# Offset.net
KiCad netlist of a schematic drawn in Altium Designer
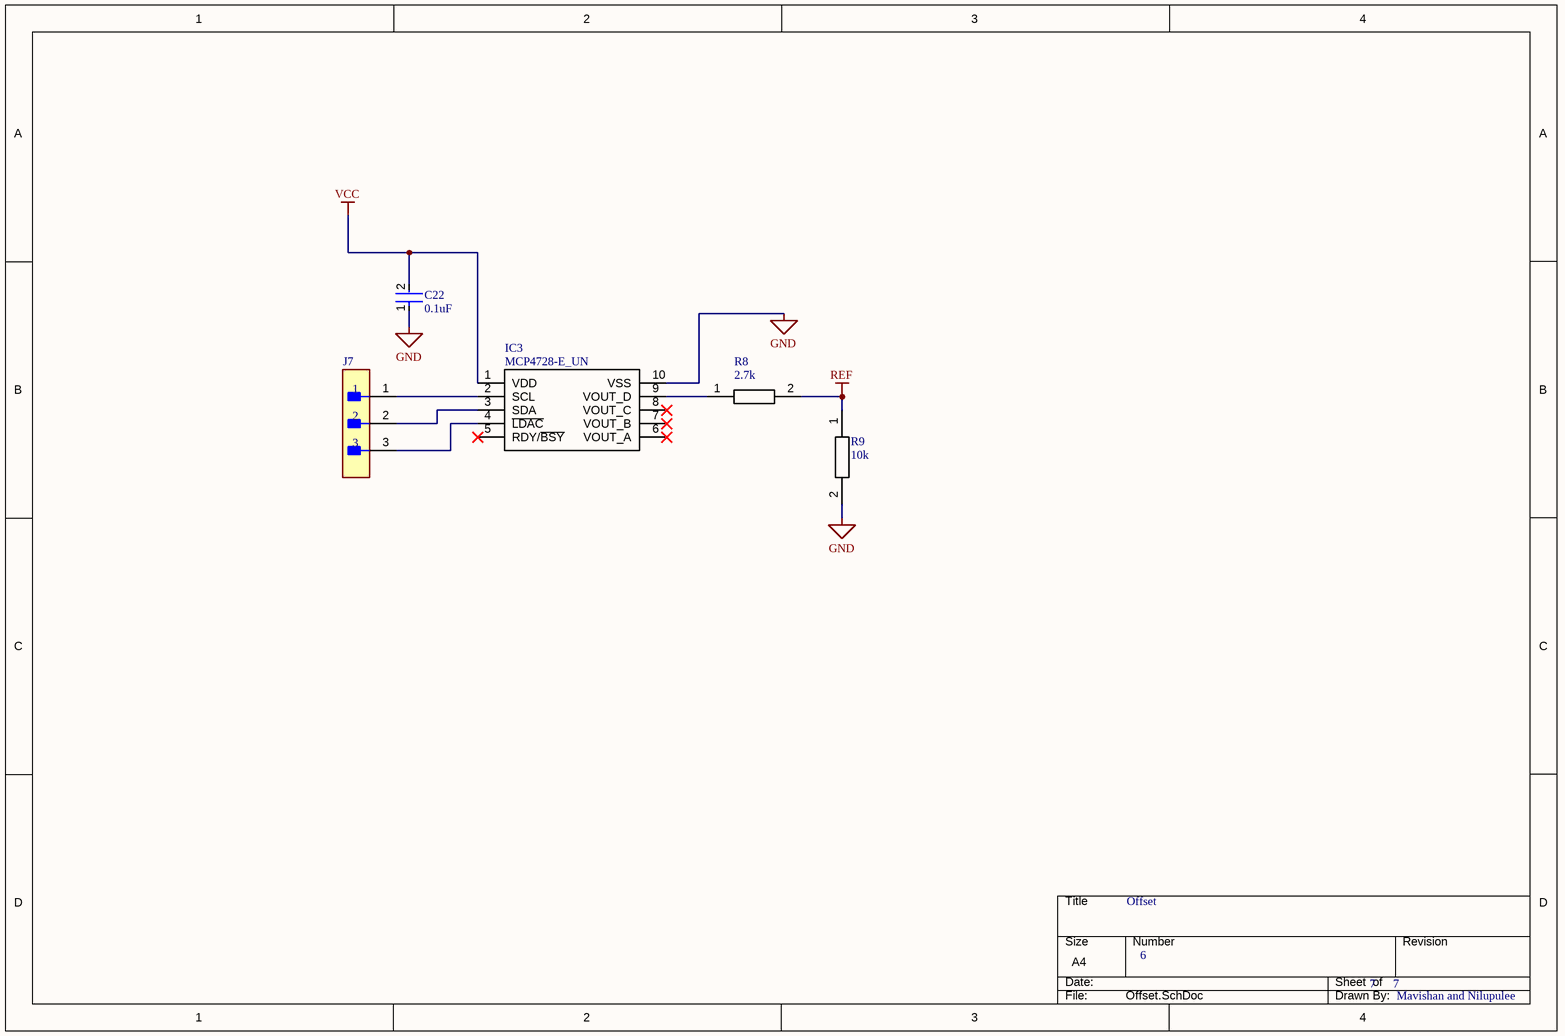
[diagram p0: Offset.SchDoc]

(export (version "E")
  (design (tool "Eeschema 10.0.6"))
  (components
    (comp (ref "C22")
      (value "0.1uF")
      (footprint "FP-C1206C-EB-MFG")
      (description "CAP CER 0.1UF 25V C0G/NP0 1206")
      (fields
        (field (name "MANUFACTURER") "KEMET")
        (field (name "MANUFACTURER PART NUMBER") "C1206C104F3GACTU")
      )
      (libsource (lib "Altium Content Vault") (part "b4654b650e69147ec39a6b967a45e02"))
    )
    (comp (ref "IC3")
      (value "MCP4728-E_UN")
      (footprint "SamacSys:SOP50P490X110-10N")
      (description "Integrated Circuit")
      (fields
        (field (name "MANUFACTURER_PART_NUMBER") "MCP4728-E/UN")
        (field (name "MOUSER PART NUMBER") "579-MCP4728-E/UN")
      )
      (libsource (lib "*") (part "MCP4728-E_UN"))
    )
    (comp (ref "J7")
      (value "B3B-XH-A(LF)(SN)")
      (footprint "FP-B3B-XH-A_LF_SN-MFG")
      (description "CONN HEADER VERT 3POS 2.5MM")
      (libsource (lib "Altium Content Vault") (part "0d3f023dd272f625e17a2be33dea85f"))
    )
    (comp (ref "R8")
      (value "ERA-8AEB272V")
      (footprint "SamacSys:RESC3216X70N")
      (description "Resistor")
      (fields (field (name "MOUSER PART NUMBER") "667-ERA-8AEB272V") (field (name "PARAMETER 1") "2.7k"))
      (libsource (lib "*") (part "ERA-8AEB272V"))
    )
    (comp (ref "R9")
      (value "ERA-8AEB103V")
      (footprint "SamacSys:RESC3216X70N")
      (description "Resistor")
      (fields (field (name "MOUSER PART NUMBER") "667-ERA-8AEB103V") (field (name "PARAMETER 1") "10k"))
      (libsource (lib "SamacSys") (part "ERA-8AEB103V"))
    )
  )
  (nets
    (net (code "1") (name "GND") (class "Default")
      (node (ref "C22") (pin "1") (pinfunction "1_1") (pintype "passive"))
      (node (ref "IC3") (pin "10") (pinfunction "VSS_10") (pintype "passive"))
      (node (ref "R9") (pin "2") (pinfunction "2_2") (pintype "passive"))
    )
    (net (code "2") (name "Net-(IC3-SCL)") (class "Default")
      (node (ref "IC3") (pin "2") (pinfunction "SCL_2") (pintype "passive"))
      (node (ref "J7") (pin "1") (pinfunction "1_1") (pintype "passive"))
    )
    (net (code "3") (name "Net-(IC3-SDA)") (class "Default")
      (node (ref "IC3") (pin "3") (pinfunction "SDA_3") (pintype "passive"))
      (node (ref "J7") (pin "2") (pinfunction "2_2") (pintype "passive"))
    )
    (net (code "4") (name "Net-(IC3-VOUT_D)") (class "Default")
      (node (ref "IC3") (pin "9") (pinfunction "VOUT_D_9") (pintype "passive"))
      (node (ref "R8") (pin "1") (pinfunction "1_1") (pintype "passive"))
    )
    (net (code "5") (name "Net-(IC3-~{LDAC})") (class "Default")
      (node (ref "IC3") (pin "4") (pinfunction "~{LDAC}_4") (pintype "passive"))
      (node (ref "J7") (pin "3") (pinfunction "3_3") (pintype "passive"))
    )
    (net (code "6") (name "REF") (class "Default")
      (node (ref "R8") (pin "2") (pinfunction "2_2") (pintype "passive"))
      (node (ref "R9") (pin "1") (pinfunction "1_1") (pintype "passive"))
    )
    (net (code "7") (name "VCC") (class "Default")
      (node (ref "C22") (pin "2") (pinfunction "2_2") (pintype "passive"))
      (node (ref "IC3") (pin "1") (pinfunction "VDD_1") (pintype "passive"))
    )
    (net (code "8") (name "unconnected-(IC3-RDY{slash}~{BSY}-Pad5)") (class "Default")
      (node (ref "IC3") (pin "5") (pinfunction "RDY/~{BSY}_5") (pintype "passive+no_connect"))
    )
    (net (code "9") (name "unconnected-(IC3-VOUT_A-Pad6)") (class "Default")
      (node (ref "IC3") (pin "6") (pinfunction "VOUT_A_6") (pintype "passive+no_connect"))
    )
    (net (code "10") (name "unconnected-(IC3-VOUT_B-Pad7)") (class "Default")
      (node (ref "IC3") (pin "7") (pinfunction "VOUT_B_7") (pintype "passive+no_connect"))
    )
    (net (code "11") (name "unconnected-(IC3-VOUT_C-Pad8)") (class "Default")
      (node (ref "IC3") (pin "8") (pinfunction "VOUT_C_8") (pintype "passive+no_connect"))
    )
  )
)
